# BK1096_MIPI_CAM.net
KiCad netlist of a schematic drawn in Altium Designer
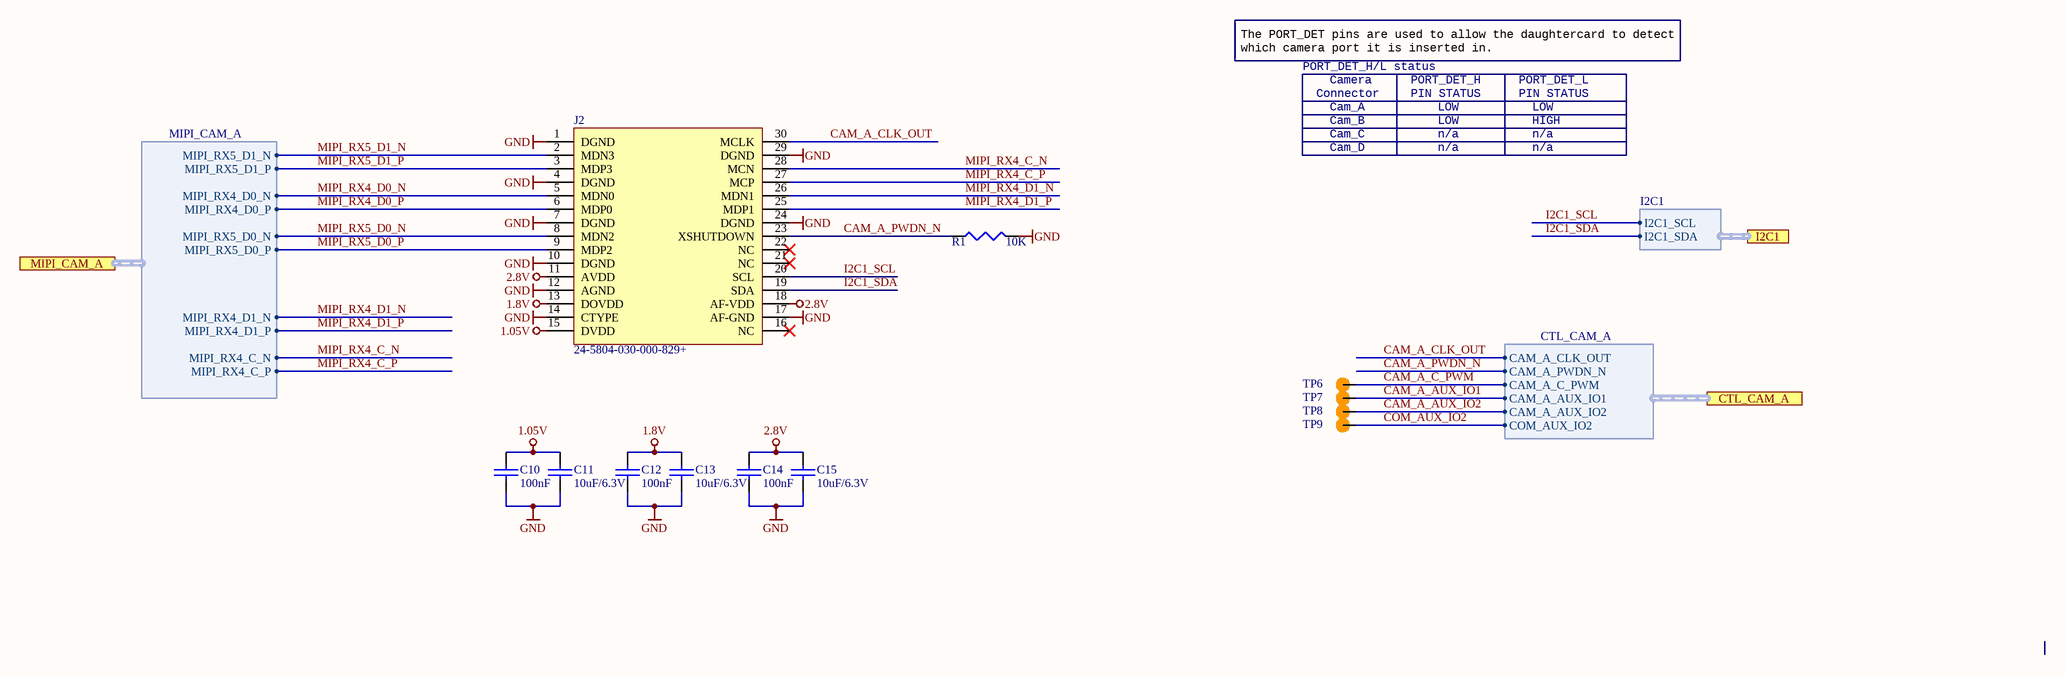
[diagram p0: BK1096_MIPI_CAM.SchDoc]

(export (version "E")
  (design (tool "Eeschema 10.0.6"))
  (components
    (comp (ref "C10")
      (value "100nF")
      (footprint "CAPC0402(1005)60_N")
      (description "SMD Multilayer Ceramic Capacitor, 0402 [1005 Metric], 0.1 µF, 10 V, ± 10%, X5R")
      (libsource (lib "MV0249_R0M0E0") (part "CAP"))
    )
    (comp (ref "C11")
      (value "10uF/6.3V")
      (footprint "CAPC0603(1608)55_N")
      (description "SMD Multilayer Ceramic Capacitor, 0603 [1608 Metric], 10 µF, 6.3 V, ± 20%, X5R")
      (libsource (lib "MV0249_R0M0E0") (part "CAP"))
    )
    (comp (ref "C12")
      (value "100nF")
      (footprint "CAPC0402(1005)60_N")
      (description "SMD Multilayer Ceramic Capacitor, 0402 [1005 Metric], 0.1 µF, 10 V, ± 10%, X5R")
      (libsource (lib "MV0249_R0M0E0") (part "CAP"))
    )
    (comp (ref "C13")
      (value "10uF/6.3V")
      (footprint "CAPC0603(1608)55_N")
      (description "SMD Multilayer Ceramic Capacitor, 0603 [1608 Metric], 10 µF, 6.3 V, ± 20%, X5R")
      (libsource (lib "MV0249_R0M0E0") (part "CAP"))
    )
    (comp (ref "C14")
      (value "100nF")
      (footprint "CAPC0402(1005)60_N")
      (description "SMD Multilayer Ceramic Capacitor, 0402 [1005 Metric], 0.1 µF, 10 V, ± 10%, X5R")
      (libsource (lib "MV0249_R0M0E0") (part "CAP"))
    )
    (comp (ref "C15")
      (value "10uF/6.3V")
      (footprint "CAPC0603(1608)55_N")
      (description "SMD Multilayer Ceramic Capacitor, 0603 [1608 Metric], 10 µF, 6.3 V, ± 20%, X5R")
      (libsource (lib "MV0249_R0M0E0") (part "CAP"))
    )
    (comp (ref "J2")
      (value "24-5804-030-000-829+")
      (footprint "LuxonisMaster:A12N02A-201_MatedModule")
      (description "Series 5804 board to board 0.4mm pitch 30 way connector")
      (libsource (lib "Luxonis") (part "A12N02A-201"))
    )
    (comp (ref "R1")
      (value "10K")
      (footprint "RESC0603(1608)_N")
      (description "SMD Chip Resistor, 10 kohm, 75 V, 0603 [1608 Metric], 100 mW, ± 1%")
      (libsource (lib "MV0249_R0M0E0") (part "RES1"))
    )
    (comp (ref "TP6")
      (value "TP_SMD")
      (footprint "TP_0.75MM_SMD_NO-SILK")
      (description "circular pad test point, SMD")
      (libsource (lib "Luxonis") (part "TP_SMD"))
    )
    (comp (ref "TP7")
      (value "TP_SMD")
      (footprint "TP_0.75MM_SMD_NO-SILK")
      (description "circular pad test point, SMD")
      (libsource (lib "Luxonis") (part "TP_SMD"))
    )
    (comp (ref "TP8")
      (value "TP_SMD")
      (footprint "TP_0.75MM_SMD_NO-SILK")
      (description "circular pad test point, SMD")
      (libsource (lib "Luxonis") (part "TP_SMD"))
    )
    (comp (ref "TP9")
      (value "TP_SMD")
      (footprint "TP_0.75MM_SMD_NO-SILK")
      (description "circular pad test point, SMD")
      (libsource (lib "Luxonis") (part "TP_SMD"))
    )
  )
  (nets
    (net (code "4") (name "/CAM_A_AUX_IO1") (class "Default")
      (node (ref "TP7") (pin "1") (pintype "passive"))
    )
    (net (code "5") (name "/CAM_A_AUX_IO2") (class "Default")
      (node (ref "TP8") (pin "1") (pintype "passive"))
    )
    (net (code "6") (name "/CAM_A_CLK_OUT") (class "Default")
      (node (ref "J2") (pin "30") (pinfunction "MCLK_30") (pintype "passive"))
    )
    (net (code "7") (name "/CAM_A_C_PWM") (class "Default") (node (ref "TP6") (pin "1") (pintype "passive")))
    (net (code "8") (name "/CAM_A_PWDN_N") (class "Default")
      (node (ref "J2") (pin "23") (pinfunction "XSHUTDOWN_23") (pintype "passive"))
      (node (ref "R1") (pin "1") (pintype "passive"))
    )
    (net (code "9") (name "/COM_AUX_IO2") (class "Default") (node (ref "TP9") (pin "1") (pintype "passive")))
    (net (code "10") (name "/I2C1_SCL") (class "Default")
      (node (ref "J2") (pin "20") (pinfunction "SCL_20") (pintype "passive"))
    )
    (net (code "11") (name "/I2C1_SDA") (class "Default")
      (node (ref "J2") (pin "19") (pinfunction "SDA_19") (pintype "passive"))
    )
    (net (code "12") (name "/MIPI_RX4_C_N") (class "Default")
      (node (ref "J2") (pin "28") (pinfunction "MCN_28") (pintype "passive"))
    )
    (net (code "13") (name "/MIPI_RX4_C_P") (class "Default")
      (node (ref "J2") (pin "27") (pinfunction "MCP_27") (pintype "passive"))
    )
    (net (code "14") (name "/MIPI_RX4_D0_N") (class "Default")
      (node (ref "J2") (pin "5") (pinfunction "MDN0_5") (pintype "passive"))
    )
    (net (code "15") (name "/MIPI_RX4_D0_P") (class "Default")
      (node (ref "J2") (pin "6") (pinfunction "MDP0_6") (pintype "passive"))
    )
    (net (code "16") (name "/MIPI_RX4_D1_N") (class "Default")
      (node (ref "J2") (pin "26") (pinfunction "MDN1_26") (pintype "passive"))
    )
    (net (code "17") (name "/MIPI_RX4_D1_P") (class "Default")
      (node (ref "J2") (pin "25") (pinfunction "MDP1_25") (pintype "passive"))
    )
    (net (code "18") (name "/MIPI_RX5_D0_N") (class "Default")
      (node (ref "J2") (pin "8") (pinfunction "MDN2_8") (pintype "passive"))
    )
    (net (code "19") (name "/MIPI_RX5_D0_P") (class "Default")
      (node (ref "J2") (pin "9") (pinfunction "MDP2_9") (pintype "passive"))
    )
    (net (code "20") (name "/MIPI_RX5_D1_N") (class "Default")
      (node (ref "J2") (pin "2") (pinfunction "MDN3_2") (pintype "passive"))
    )
    (net (code "21") (name "/MIPI_RX5_D1_P") (class "Default")
      (node (ref "J2") (pin "3") (pinfunction "MDP3_3") (pintype "passive"))
    )
    (net (code "25") (name "1.05V") (class "Default")
      (node (ref "C10") (pin "2") (pinfunction "2_2") (pintype "passive"))
      (node (ref "C11") (pin "2") (pinfunction "2_2") (pintype "passive"))
      (node (ref "J2") (pin "15") (pinfunction "DVDD_15") (pintype "passive"))
    )
    (net (code "26") (name "1.8V") (class "Default")
      (node (ref "C12") (pin "2") (pinfunction "2_2") (pintype "passive"))
      (node (ref "C13") (pin "2") (pinfunction "2_2") (pintype "passive"))
      (node (ref "J2") (pin "13") (pinfunction "DOVDD_13") (pintype "passive"))
    )
    (net (code "27") (name "2.8V") (class "Default")
      (node (ref "C14") (pin "2") (pinfunction "2_2") (pintype "passive"))
      (node (ref "C15") (pin "2") (pinfunction "2_2") (pintype "passive"))
      (node (ref "J2") (pin "11") (pinfunction "AVDD_11") (pintype "passive"))
      (node (ref "J2") (pin "18") (pinfunction "AF-VDD_18") (pintype "passive"))
    )
    (net (code "28") (name "GND") (class "Default")
      (node (ref "C10") (pin "1") (pinfunction "1_1") (pintype "passive"))
      (node (ref "C11") (pin "1") (pinfunction "1_1") (pintype "passive"))
      (node (ref "C12") (pin "1") (pinfunction "1_1") (pintype "passive"))
      (node (ref "C13") (pin "1") (pinfunction "1_1") (pintype "passive"))
      (node (ref "C14") (pin "1") (pinfunction "1_1") (pintype "passive"))
      (node (ref "C15") (pin "1") (pinfunction "1_1") (pintype "passive"))
      (node (ref "J2") (pin "1") (pinfunction "DGND_1") (pintype "passive"))
      (node (ref "J2") (pin "10") (pinfunction "DGND_10") (pintype "passive"))
      (node (ref "J2") (pin "12") (pinfunction "AGND_12") (pintype "passive"))
      (node (ref "J2") (pin "14") (pinfunction "CTYPE_14") (pintype "passive"))
      (node (ref "J2") (pin "17") (pinfunction "AF-GND_17") (pintype "passive"))
      (node (ref "J2") (pin "24") (pinfunction "DGND_24") (pintype "passive"))
      (node (ref "J2") (pin "29") (pinfunction "DGND_29") (pintype "passive"))
      (node (ref "J2") (pin "4") (pinfunction "DGND_4") (pintype "passive"))
      (node (ref "J2") (pin "7") (pinfunction "DGND_7") (pintype "passive"))
      (node (ref "R1") (pin "2") (pintype "passive"))
    )
    (net (code "29") (name "unconnected-(J2-NC-Pad16)") (class "Default")
      (node (ref "J2") (pin "16") (pinfunction "NC_16") (pintype "passive+no_connect"))
    )
    (net (code "30") (name "unconnected-(J2-NC-Pad21)") (class "Default")
      (node (ref "J2") (pin "21") (pinfunction "NC_21") (pintype "passive+no_connect"))
    )
    (net (code "31") (name "unconnected-(J2-NC-Pad22)") (class "Default")
      (node (ref "J2") (pin "22") (pinfunction "NC_22") (pintype "passive+no_connect"))
    )
  )
)
